# rgb-nir-uv-stalk.net
KiCad netlist of a schematic drawn in EAGLE
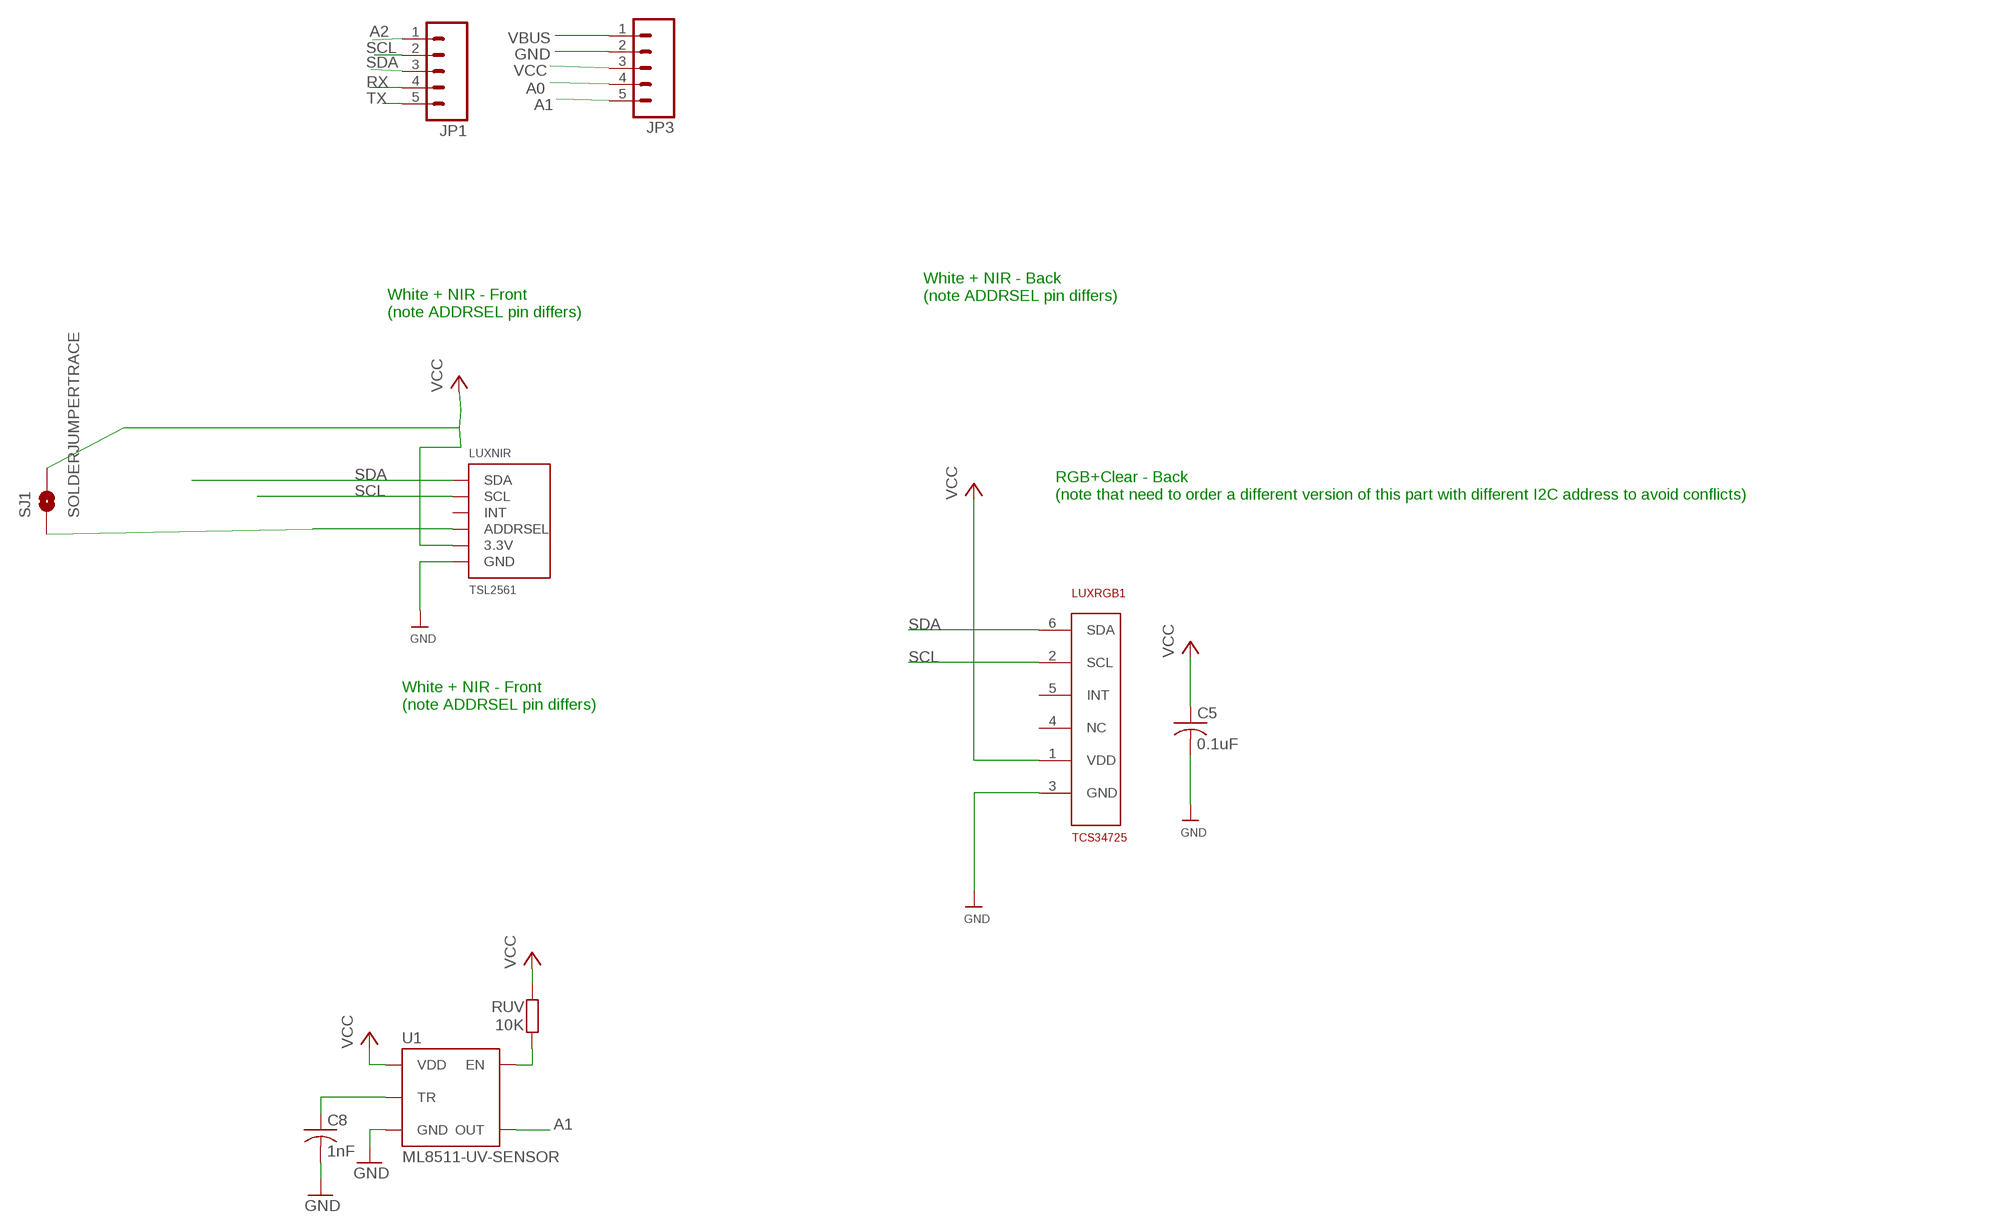
[diagram p0: schematic, sheet 1]

(export (version "E")
  (design (tool "Eeschema 10.0.6"))
  (components
    (comp (ref "C5")
      (value "0.1uF")
      (footprint "eagle-import:C0805")
      (libsource (lib "eagle-import") (part "C-USC0805"))
    )
    (comp (ref "C8")
      (value "1nF")
      (footprint "eagle-import:C0805")
      (libsource (lib "eagle-import") (part "C-USC0805"))
    )
    (comp (ref "JP1")
      (value "M05LOCK")
      (footprint "eagle-import:1X05_LOCK")
      (libsource (lib "eagle-import") (part "M05LOCK"))
    )
    (comp (ref "JP3")
      (value "M05LOCK")
      (footprint "eagle-import:1X05_LOCK")
      (libsource (lib "eagle-import") (part "M05LOCK"))
    )
    (comp (ref "LUXNIR")
      (value "TSL2561")
      (footprint "eagle-import:TSL2561_FN@1")
      (libsource (lib "eagle-import") (part "TSL2561"))
    )
    (comp (ref "LUXRGB1")
      (value "TCS34725")
      (footprint "eagle-import:DFN-6")
      (libsource (lib "eagle-import") (part "TCS34725"))
    )
    (comp (ref "RUV")
      (value "10K")
      (footprint "eagle-import:R0805")
      (libsource (lib "eagle-import") (part "R-EU_R0805"))
    )
    (comp (ref "SJ1")
      (value "SOLDERJUMPERTRACE")
      (footprint "eagle-import:SJ_2S-TRACE")
      (libsource (lib "eagle-import") (part "SOLDERJUMPERTRACE"))
    )
    (comp (ref "U1")
      (value "ML8511-UV-SENSOR")
      (footprint "eagle-import:ML8511")
      (libsource (lib "eagle-import") (part "ML8511-UV-SENSORSMD"))
    )
  )
  (nets
    (net (code "1") (name "/A0") (class "Default")
      (node (ref "JP3") (pin "4") (pinfunction "4_4") (pintype "passive"))
    )
    (net (code "2") (name "/A1") (class "Default")
      (node (ref "JP3") (pin "5") (pinfunction "5_5") (pintype "passive"))
      (node (ref "U1") (pin "8") (pinfunction "OUT_8") (pintype "output"))
    )
    (net (code "3") (name "/A2") (class "Default")
      (node (ref "JP1") (pin "1") (pinfunction "1_1") (pintype "passive"))
    )
    (net (code "4") (name "/RX") (class "Default")
      (node (ref "JP1") (pin "4") (pinfunction "4_4") (pintype "passive"))
    )
    (net (code "5") (name "/SCL") (class "Default")
      (node (ref "JP1") (pin "2") (pinfunction "2_2") (pintype "passive"))
      (node (ref "LUXNIR") (pin "CLK") (pinfunction "SCL_CLK") (pintype "bidirectional"))
      (node (ref "LUXRGB1") (pin "2") (pinfunction "SCL_2") (pintype "bidirectional"))
    )
    (net (code "6") (name "/SDA") (class "Default")
      (node (ref "JP1") (pin "3") (pinfunction "3_3") (pintype "passive"))
      (node (ref "LUXNIR") (pin "DATA") (pinfunction "SDA_DATA") (pintype "bidirectional"))
      (node (ref "LUXRGB1") (pin "6") (pinfunction "SDA_6") (pintype "bidirectional"))
    )
    (net (code "7") (name "/TX") (class "Default")
      (node (ref "JP1") (pin "5") (pinfunction "5_5") (pintype "passive"))
    )
    (net (code "8") (name "/VBUS") (class "Default")
      (node (ref "JP3") (pin "1") (pinfunction "1_1") (pintype "passive"))
    )
    (net (code "9") (name "GND") (class "Default")
      (node (ref "C5") (pin "2") (pinfunction "2_2") (pintype "passive"))
      (node (ref "C8") (pin "2") (pinfunction "2_2") (pintype "passive"))
      (node (ref "JP3") (pin "2") (pinfunction "2_2") (pintype "passive"))
      (node (ref "LUXNIR") (pin "VSS") (pinfunction "GND_VSS") (pintype "bidirectional"))
      (node (ref "LUXRGB1") (pin "3") (pinfunction "GND_3") (pintype "bidirectional"))
      (node (ref "U1") (pin "5") (pinfunction "GND_5") (pintype "power_in"))
    )
    (net (code "10") (name "Net-(LUXNIR-ADDRSEL)") (class "Default")
      (node (ref "LUXNIR") (pin "ADR") (pinfunction "ADDRSEL_ADR") (pintype "bidirectional"))
      (node (ref "SJ1") (pin "1") (pinfunction "1_1") (pintype "passive"))
    )
    (net (code "11") (name "Net-(U1-EN)") (class "Default")
      (node (ref "RUV") (pin "1") (pinfunction "1_1") (pintype "passive"))
      (node (ref "U1") (pin "4") (pinfunction "EN_4") (pintype "input"))
    )
    (net (code "12") (name "Net-(U1-TR)") (class "Default")
      (node (ref "C8") (pin "1") (pinfunction "1_1") (pintype "passive"))
      (node (ref "U1") (pin "10") (pinfunction "TR_10") (pintype "power_in"))
    )
    (net (code "13") (name "VCC") (class "Default")
      (node (ref "C5") (pin "1") (pinfunction "1_1") (pintype "passive"))
      (node (ref "JP3") (pin "3") (pinfunction "3_3") (pintype "passive"))
      (node (ref "LUXNIR") (pin "VDD") (pinfunction "3.3V_VDD") (pintype "bidirectional"))
      (node (ref "LUXRGB1") (pin "1") (pinfunction "VDD_1") (pintype "bidirectional"))
      (node (ref "RUV") (pin "2") (pinfunction "2_2") (pintype "passive"))
      (node (ref "SJ1") (pin "2") (pinfunction "2_2") (pintype "passive"))
      (node (ref "U1") (pin "7") (pinfunction "VDD_7") (pintype "power_in"))
    )
    (net (code "14") (name "unconnected-(LUXNIR-PadINT)") (class "Default")
      (node (ref "LUXNIR") (pin "INT") (pinfunction "INT_INT") (pintype "bidirectional"))
    )
    (net (code "15") (name "unconnected-(LUXRGB1-INT-Pad5)") (class "Default")
      (node (ref "LUXRGB1") (pin "5") (pinfunction "INT_5") (pintype "bidirectional"))
    )
    (net (code "16") (name "unconnected-(LUXRGB1-NC-Pad4)") (class "Default")
      (node (ref "LUXRGB1") (pin "4") (pinfunction "NC_4") (pintype "bidirectional"))
    )
  )
)
